# PiOBD_CM4_RTC.net
KiCad netlist of a schematic drawn in Altium Designer
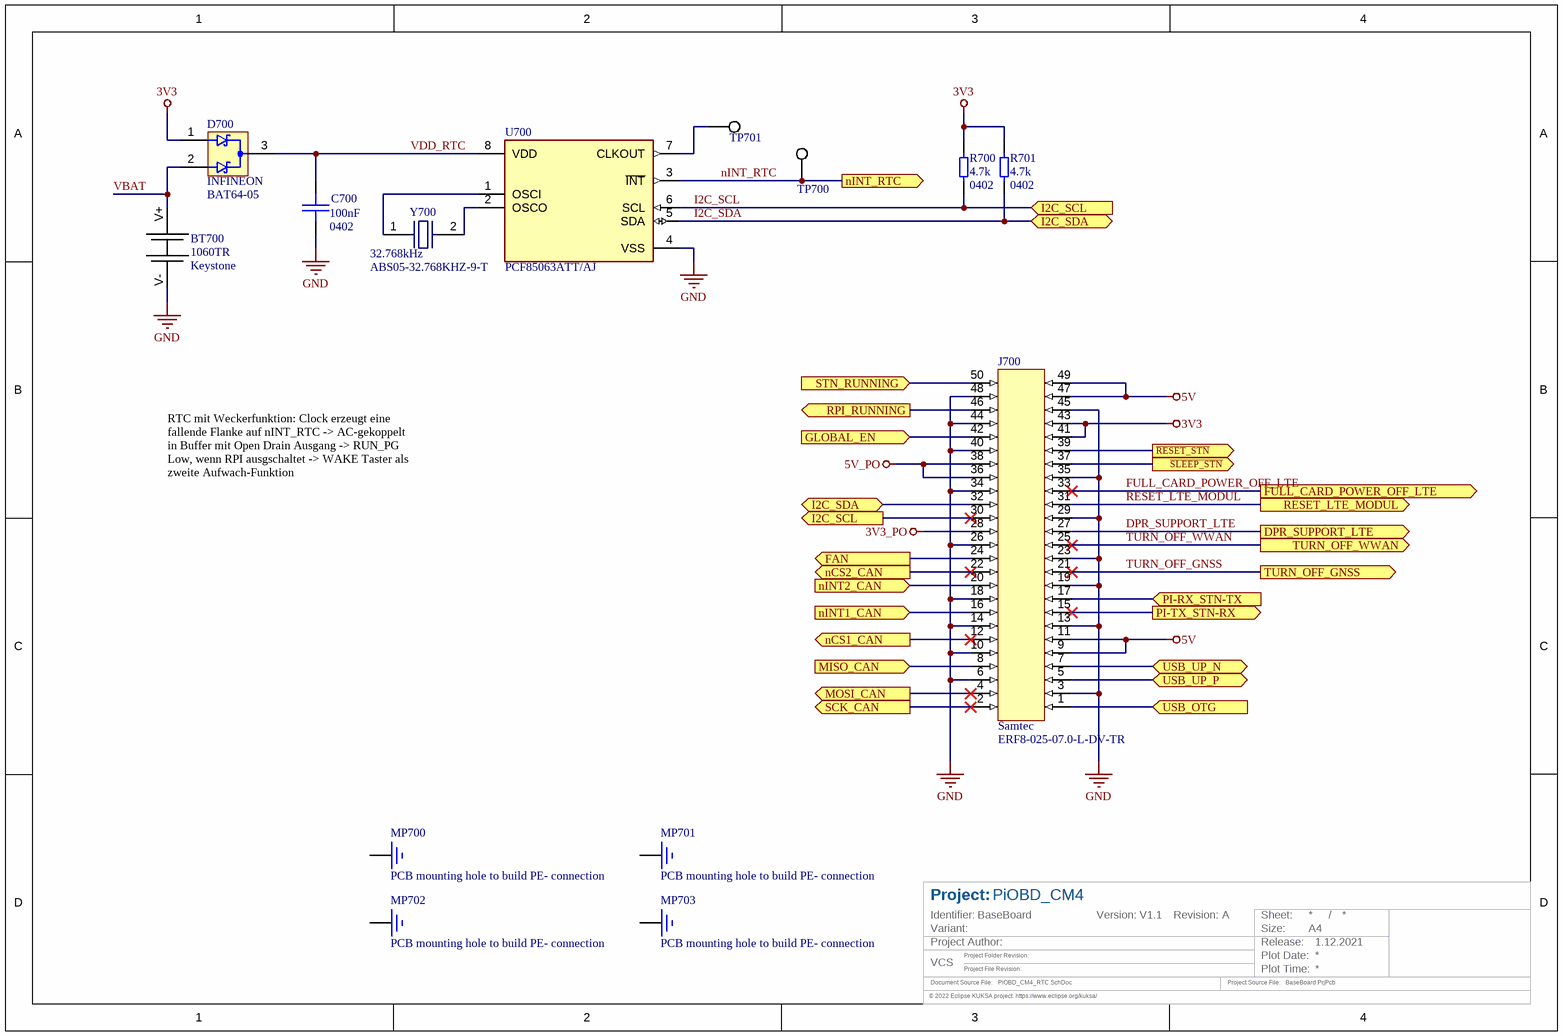
[diagram p0: PiOBD_CM4_RTC.SchDoc]

(export (version "E")
  (design (tool "Eeschema 10.0.6"))
  (components
    (comp (ref "BT700")
      (value "KEYSTONE - 1060")
      (footprint "KEYSTONE - 1060-Footprint-1")
      (description "Batterie Halter (offen) Kreisförmige Scheibe, 20,0mm 1 Zellen SMD (SMT) Tab")
      (fields (field (name "MANUFACTURER PART NUMBER") "1060TR") (field (name "MANUFACTURER") "Keystone"))
      (libsource (lib "ShareLib") (part "KEYSTONE - 1060"))
    )
    (comp (ref "C700")
      (value "CAP 0402 100n -10% +10% 6.3V X7R")
      (footprint "CAP 0402 [1005 Metric] X050 N")
      (description "SMD/SMT 0402 6.3V -10% +10% X7R - Multilayer Ceramic Capacitors MLCC")
      (fields
        (field (name "MANUFACTURER") "MURATA")
        (field (name "CAPACITANCE") "100nF")
        (field (name "MANUFACTURER PART NUMBER") "GRM155R70J104KA01#")
        (field (name "CASE") "0402")
      )
      (libsource (lib "ShareLib") (part "Capacitor non-polarized - Standard Schematic"))
    )
    (comp (ref "D700")
      (value "INFINEON - BAT64-05")
      (footprint "INFINEON - BAT64-04")
      (description "Dual Silicon Schottky Diodes")
      (fields (field (name "MANUFACTURER") "INFINEON") (field (name "MANUFACTURER PART NUMBER") "BAT64-05"))
      (libsource (lib "ShareLib") (part "Dual Schottky barrier rectifier"))
    )
    (comp (ref "J700")
      (value "SAMTEC - ERF8-025-07.0-L-DV-TR")
      (footprint "SAMTEC - ERF-025-05.0-L-DV-TR-Footprint-1")
      (description "50 Poliger Steckverbinder Sockel, äußere Abdeckungskontakte Oberflächenmontage Gold")
      (fields
        (field (name "MANUFACTURER") "Samtec")
        (field (name "MANUFACTURER PART NUMBER") "ERF8-025-07.0-L-DV-TR")
      )
      (libsource (lib "ShareLib") (part "SAMTEC - ERF8-025-07.0-L-DV-TR"))
    )
    (comp (ref "MP700")
      (value "PCB mounting hole to build PE- connection")
      (footprint "MountingPad")
      (description "PCB mounting hole to build PE- connection, hole diameter 4.3mm")
      (libsource (lib "ShareLib") (part "PCB mounting hole (no BOM)"))
    )
    (comp (ref "MP701")
      (value "PCB mounting hole to build PE- connection")
      (footprint "MountingPad")
      (description "PCB mounting hole to build PE- connection, hole diameter 4.3mm")
      (libsource (lib "ShareLib") (part "PCB mounting hole (no BOM)"))
    )
    (comp (ref "MP702")
      (value "PCB mounting hole to build PE- connection")
      (footprint "MountingPad")
      (description "PCB mounting hole to build PE- connection, hole diameter 4.3mm")
      (libsource (lib "ShareLib") (part "PCB mounting hole (no BOM)"))
    )
    (comp (ref "MP703")
      (value "PCB mounting hole to build PE- connection")
      (footprint "MountingPad")
      (description "PCB mounting hole to build PE- connection, hole diameter 4.3mm")
      (libsource (lib "ShareLib") (part "PCB mounting hole (no BOM)"))
    )
    (comp (ref "R700")
      (value "RES 0402 4K7 1% 0W0625")
      (footprint "RES 0402 [1005 Metric]_N")
      (description "RC0402 series chip resistor with lead-free terminations made by thick film process")
      (fields
        (field (name "RESISTANCE") "4.7k")
        (field (name "MANUFACTURER PART NUMBER") "RC0402FR-074K7L")
        (field (name "MANUFACTURER") "YAGEO")
        (field (name "CASE") "0402")
      )
      (libsource (lib "ShareLib") (part "Standard Schematic - Resistor Universal"))
    )
    (comp (ref "R701")
      (value "RES 0402 4K7 1% 0W0625")
      (footprint "RES 0402 [1005 Metric]_N")
      (description "RC0402 series chip resistor with lead-free terminations made by thick film process")
      (fields
        (field (name "RESISTANCE") "4.7k")
        (field (name "MANUFACTURER PART NUMBER") "RC0402FR-074K7L")
        (field (name "MANUFACTURER") "YAGEO")
        (field (name "CASE") "0402")
      )
      (libsource (lib "ShareLib") (part "Standard Schematic - Resistor Universal"))
    )
    (comp (ref "TP700")
      (value "Testpad, 0.8mm x 0.8mm, round")
      (footprint "Testpad, 0.8mm x 0.8mm, round")
      (libsource (lib "ShareLib") (part "Testpoint (No BOM)"))
    )
    (comp (ref "TP701")
      (value "Testpad, 0.8mm x 0.8mm, round")
      (footprint "Testpad, 0.8mm x 0.8mm, round")
      (libsource (lib "ShareLib") (part "Testpoint (No BOM)"))
    )
    (comp (ref "U700")
      (value "PCF85063ATT/AJ")
      (footprint "FP-SOT505-1-MFG")
      (description "IC RTC CLK/CALENDAR I2C 8TSSOP")
      (fields
        (field (name "OCTOPART") "https://octopart.com/pcf85063att%2Faj-nxp+semiconductors-46729225")
        (field (name "MANUFACTURER") "NXP Semiconductors")
      )
      (libsource (lib "Altium Content Vault") (part "824269ce6ab1022c00e763b986ab016"))
    )
    (comp (ref "Y700")
      (value "ABRACON - ABS05-32.768KHZ-9-T")
      (footprint "ABRACON - ABS05-32.768KHZ-9-T")
      (description "Crystals 32.768KHz 9.0pF 20ppm -40C +85C")
      (fields
        (field (name "MANUFACTURER") "ABRACON")
        (field (name "MANUFACTURER PART NUMBER") "ABS05-32.768KHZ-9-T")
        (field (name "FREQUENCY") "32.768kHz")
      )
      (libsource (lib "ShareLib") (part "Component_1"))
    )
  )
  (nets
    (net (code "1") (name "/DPR_SUPPORT_LTE") (class "Default")
      (node (ref "J700") (pin "27") (pintype "input"))
    )
    (net (code "2") (name "/FAN") (class "Default") (node (ref "J700") (pin "24") (pintype "input")))
    (net (code "3") (name "/FULL_CARD_POWER_OFF_LTE") (class "Default")
      (node (ref "J700") (pin "33") (pintype "input+no_connect"))
    )
    (net (code "4") (name "/GLOBAL_EN") (class "Default") (node (ref "J700") (pin "42") (pintype "input")))
    (net (code "5") (name "/I2C_SCL") (class "Default")
      (node (ref "J700") (pin "30") (pintype "input"))
      (node (ref "R700") (pin "1") (pinfunction "1_1") (pintype "passive"))
      (node (ref "U700") (pin "6") (pinfunction "SCL_6") (pintype "input"))
    )
    (net (code "6") (name "/I2C_SDA") (class "Default")
      (node (ref "J700") (pin "32") (pintype "input"))
      (node (ref "R701") (pin "1") (pinfunction "1_1") (pintype "passive"))
      (node (ref "U700") (pin "5") (pinfunction "SDA_5") (pintype "bidirectional"))
    )
    (net (code "7") (name "/MISO_CAN") (class "Default") (node (ref "J700") (pin "8") (pintype "input")))
    (net (code "8") (name "/MOSI_CAN") (class "Default")
      (node (ref "J700") (pin "4") (pintype "input+no_connect"))
    )
    (net (code "9") (name "/PI-RX_STN-TX") (class "Default") (node (ref "J700") (pin "17") (pintype "input")))
    (net (code "10") (name "/PI-TX_STN-RX") (class "Default")
      (node (ref "J700") (pin "15") (pintype "input+no_connect"))
    )
    (net (code "11") (name "/RESET_LTE_MODUL") (class "Default")
      (node (ref "J700") (pin "31") (pintype "input"))
    )
    (net (code "12") (name "/RESET_STN") (class "Default") (node (ref "J700") (pin "39") (pintype "input")))
    (net (code "13") (name "/RPI_RUNNING") (class "Default") (node (ref "J700") (pin "46") (pintype "input")))
    (net (code "14") (name "/SCK_CAN") (class "Default")
      (node (ref "J700") (pin "2") (pintype "input+no_connect"))
    )
    (net (code "15") (name "/SLEEP_STN") (class "Default") (node (ref "J700") (pin "37") (pintype "input")))
    (net (code "16") (name "/STN_RUNNING") (class "Default") (node (ref "J700") (pin "50") (pintype "input")))
    (net (code "17") (name "/TURN_OFF_GNSS") (class "Default")
      (node (ref "J700") (pin "21") (pintype "input+no_connect"))
    )
    (net (code "18") (name "/TURN_OFF_WWAN") (class "Default")
      (node (ref "J700") (pin "25") (pintype "input+no_connect"))
    )
    (net (code "19") (name "/USB_OTG") (class "Default") (node (ref "J700") (pin "1") (pintype "input")))
    (net (code "20") (name "/USB_UP_N") (class "Default") (node (ref "J700") (pin "7") (pintype "input")))
    (net (code "21") (name "/USB_UP_P") (class "Default") (node (ref "J700") (pin "5") (pintype "input")))
    (net (code "22") (name "/VBAT") (class "Default")
      (node (ref "BT700") (pin "V+") (pintype "power_in"))
      (node (ref "D700") (pin "2") (pinfunction "2_2") (pintype "passive"))
    )
    (net (code "23") (name "/VDD_RTC") (class "Default")
      (node (ref "C700") (pin "2") (pinfunction "2_2") (pintype "passive"))
      (node (ref "D700") (pin "3") (pinfunction "3_3") (pintype "passive"))
      (node (ref "U700") (pin "8") (pinfunction "VDD_8") (pintype "power_in"))
    )
    (net (code "24") (name "/nCS1_CAN") (class "Default")
      (node (ref "J700") (pin "12") (pintype "input+no_connect"))
    )
    (net (code "25") (name "/nCS2_CAN") (class "Default")
      (node (ref "J700") (pin "22") (pintype "input+no_connect"))
    )
    (net (code "26") (name "/nINT1_CAN") (class "Default") (node (ref "J700") (pin "16") (pintype "input")))
    (net (code "27") (name "/nINT2_CAN") (class "Default") (node (ref "J700") (pin "20") (pintype "input")))
    (net (code "28") (name "/nINT_RTC") (class "Default")
      (node (ref "TP700") (pin "1") (pinfunction "1_1") (pintype "passive"))
      (node (ref "U700") (pin "3") (pinfunction "~{INT}_3") (pintype "output"))
    )
    (net (code "29") (name "3V3") (class "Default")
      (node (ref "D700") (pin "1") (pinfunction "1_1") (pintype "passive"))
      (node (ref "J700") (pin "41") (pintype "input"))
      (node (ref "J700") (pin "43") (pintype "input"))
      (node (ref "R700") (pin "2") (pinfunction "2_2") (pintype "passive"))
      (node (ref "R701") (pin "2") (pinfunction "2_2") (pintype "passive"))
    )
    (net (code "30") (name "3V3_PO") (class "Default") (node (ref "J700") (pin "28") (pintype "input")))
    (net (code "31") (name "5V") (class "Default")
      (node (ref "J700") (pin "11") (pintype "input"))
      (node (ref "J700") (pin "47") (pintype "input"))
      (node (ref "J700") (pin "49") (pintype "input"))
      (node (ref "J700") (pin "9") (pintype "input"))
    )
    (net (code "32") (name "5V_PO") (class "Default")
      (node (ref "J700") (pin "36") (pintype "input"))
      (node (ref "J700") (pin "38") (pintype "input"))
    )
    (net (code "33") (name "GND") (class "Default")
      (node (ref "BT700") (pin "V-") (pintype "power_in"))
      (node (ref "C700") (pin "1") (pinfunction "1_1") (pintype "passive"))
      (node (ref "J700") (pin "10") (pintype "input"))
      (node (ref "J700") (pin "13") (pintype "input"))
      (node (ref "J700") (pin "14") (pintype "input"))
      (node (ref "J700") (pin "18") (pintype "input"))
      (node (ref "J700") (pin "19") (pintype "input"))
      (node (ref "J700") (pin "23") (pintype "input"))
      (node (ref "J700") (pin "26") (pintype "input"))
      (node (ref "J700") (pin "29") (pintype "input"))
      (node (ref "J700") (pin "3") (pintype "input"))
      (node (ref "J700") (pin "34") (pintype "input"))
      (node (ref "J700") (pin "35") (pintype "input"))
      (node (ref "J700") (pin "40") (pintype "input"))
      (node (ref "J700") (pin "44") (pintype "input"))
      (node (ref "J700") (pin "45") (pintype "input"))
      (node (ref "J700") (pin "48") (pintype "input"))
      (node (ref "J700") (pin "6") (pintype "input"))
      (node (ref "U700") (pin "4") (pinfunction "VSS_4") (pintype "power_in"))
    )
    (net (code "34") (name "Net-(U700-CLKOUT)") (class "Default")
      (node (ref "TP701") (pin "1") (pinfunction "1_1") (pintype "passive"))
      (node (ref "U700") (pin "7") (pinfunction "CLKOUT_7") (pintype "output"))
    )
    (net (code "35") (name "Net-(U700-OSCI)") (class "Default")
      (node (ref "U700") (pin "1") (pinfunction "OSCI_1") (pintype "passive"))
      (node (ref "Y700") (pin "1") (pinfunction "1_1") (pintype "passive"))
    )
    (net (code "36") (name "Net-(U700-OSCO)") (class "Default")
      (node (ref "U700") (pin "2") (pinfunction "OSCO_2") (pintype "passive"))
      (node (ref "Y700") (pin "2") (pinfunction "2_2") (pintype "passive"))
    )
    (net (code "37") (name "unconnected-(MP700-PE-Pad1)") (class "Default")
      (node (ref "MP700") (pin "1") (pinfunction "PE_1") (pintype "passive"))
    )
    (net (code "38") (name "unconnected-(MP701-PE-Pad1)") (class "Default")
      (node (ref "MP701") (pin "1") (pinfunction "PE_1") (pintype "passive"))
    )
    (net (code "39") (name "unconnected-(MP702-PE-Pad1)") (class "Default")
      (node (ref "MP702") (pin "1") (pinfunction "PE_1") (pintype "passive"))
    )
    (net (code "40") (name "unconnected-(MP703-PE-Pad1)") (class "Default")
      (node (ref "MP703") (pin "1") (pinfunction "PE_1") (pintype "passive"))
    )
  )
)
